# ShiftSlice.net
KiCad netlist of a schematic drawn in EAGLE
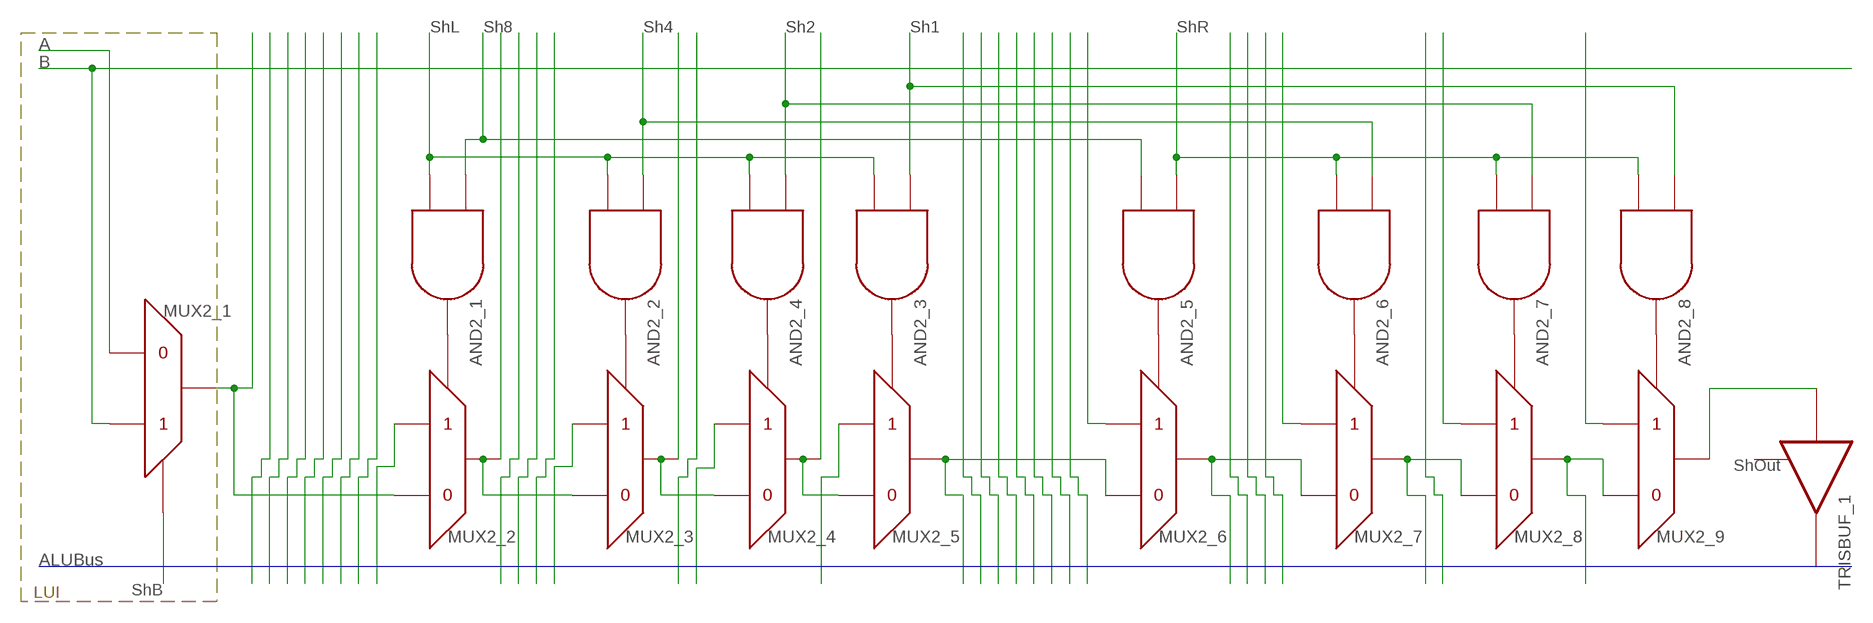
[diagram p0: schematic, sheet 1]

(export (version "E")
  (design (tool "Eeschema 10.0.6"))
  (components
    (comp (ref "AND2_1")
      (value "AND2")
      (footprint "eagle-import:3PIN")
      (libsource (lib "eagle-import") (part "AND2"))
    )
    (comp (ref "AND2_2")
      (value "AND2")
      (footprint "eagle-import:3PIN")
      (libsource (lib "eagle-import") (part "AND2"))
    )
    (comp (ref "AND2_3")
      (value "AND2")
      (footprint "eagle-import:3PIN")
      (libsource (lib "eagle-import") (part "AND2"))
    )
    (comp (ref "AND2_4")
      (value "AND2")
      (footprint "eagle-import:3PIN")
      (libsource (lib "eagle-import") (part "AND2"))
    )
    (comp (ref "AND2_5")
      (value "AND2")
      (footprint "eagle-import:3PIN")
      (libsource (lib "eagle-import") (part "AND2"))
    )
    (comp (ref "AND2_6")
      (value "AND2")
      (footprint "eagle-import:3PIN")
      (libsource (lib "eagle-import") (part "AND2"))
    )
    (comp (ref "AND2_7")
      (value "AND2")
      (footprint "eagle-import:3PIN")
      (libsource (lib "eagle-import") (part "AND2"))
    )
    (comp (ref "AND2_8")
      (value "AND2")
      (footprint "eagle-import:3PIN")
      (libsource (lib "eagle-import") (part "AND2"))
    )
    (comp (ref "MUX2_1")
      (value "MUX2")
      (footprint "eagle-import:5PIN")
      (libsource (lib "eagle-import") (part "MUX2"))
    )
    (comp (ref "MUX2_2")
      (value "MUX2")
      (footprint "eagle-import:5PIN")
      (libsource (lib "eagle-import") (part "MUX2"))
    )
    (comp (ref "MUX2_3")
      (value "MUX2")
      (footprint "eagle-import:5PIN")
      (libsource (lib "eagle-import") (part "MUX2"))
    )
    (comp (ref "MUX2_4")
      (value "MUX2")
      (footprint "eagle-import:5PIN")
      (libsource (lib "eagle-import") (part "MUX2"))
    )
    (comp (ref "MUX2_5")
      (value "MUX2")
      (footprint "eagle-import:5PIN")
      (libsource (lib "eagle-import") (part "MUX2"))
    )
    (comp (ref "MUX2_6")
      (value "MUX2")
      (footprint "eagle-import:5PIN")
      (libsource (lib "eagle-import") (part "MUX2"))
    )
    (comp (ref "MUX2_7")
      (value "MUX2")
      (footprint "eagle-import:5PIN")
      (libsource (lib "eagle-import") (part "MUX2"))
    )
    (comp (ref "MUX2_8")
      (value "MUX2")
      (footprint "eagle-import:5PIN")
      (libsource (lib "eagle-import") (part "MUX2"))
    )
    (comp (ref "MUX2_9")
      (value "MUX2")
      (footprint "eagle-import:5PIN")
      (libsource (lib "eagle-import") (part "MUX2"))
    )
    (comp (ref "TRISBUF_1")
      (value "TRISBUF")
      (footprint "eagle-import:3PIN")
      (libsource (lib "eagle-import") (part "TRISBUF"))
    )
  )
  (nets
    (net (code "1") (name "Net-(AND2_1-A)") (class "Default")
      (node (ref "AND2_1") (pin "P$1") (pinfunction "A_P$1") (pintype "input"))
      (node (ref "AND2_5") (pin "P$2") (pinfunction "I1_P$2") (pintype "input"))
    )
    (net (code "2") (name "Net-(AND2_1-I1)") (class "Default")
      (node (ref "AND2_1") (pin "P$2") (pinfunction "I1_P$2") (pintype "input"))
      (node (ref "AND2_2") (pin "P$2") (pinfunction "I1_P$2") (pintype "input"))
      (node (ref "AND2_3") (pin "P$2") (pinfunction "I1_P$2") (pintype "input"))
      (node (ref "AND2_4") (pin "P$2") (pinfunction "I1_P$2") (pintype "input"))
    )
    (net (code "3") (name "Net-(AND2_1-O)") (class "Default")
      (node (ref "AND2_1") (pin "P$3") (pinfunction "O_P$3") (pintype "output"))
      (node (ref "MUX2_2") (pin "P$4") (pinfunction "P$4_P$4") (pintype "bidirectional"))
    )
    (net (code "4") (name "Net-(AND2_2-A)") (class "Default")
      (node (ref "AND2_2") (pin "P$1") (pinfunction "A_P$1") (pintype "input"))
      (node (ref "AND2_6") (pin "P$1") (pinfunction "A_P$1") (pintype "input"))
    )
    (net (code "5") (name "Net-(AND2_2-O)") (class "Default")
      (node (ref "AND2_2") (pin "P$3") (pinfunction "O_P$3") (pintype "output"))
      (node (ref "MUX2_3") (pin "P$4") (pinfunction "P$4_P$4") (pintype "bidirectional"))
    )
    (net (code "6") (name "Net-(AND2_3-A)") (class "Default")
      (node (ref "AND2_3") (pin "P$1") (pinfunction "A_P$1") (pintype "input"))
      (node (ref "AND2_8") (pin "P$1") (pinfunction "A_P$1") (pintype "input"))
    )
    (net (code "7") (name "Net-(AND2_3-O)") (class "Default")
      (node (ref "AND2_3") (pin "P$3") (pinfunction "O_P$3") (pintype "output"))
      (node (ref "MUX2_5") (pin "P$4") (pinfunction "P$4_P$4") (pintype "bidirectional"))
    )
    (net (code "8") (name "Net-(AND2_4-A)") (class "Default")
      (node (ref "AND2_4") (pin "P$1") (pinfunction "A_P$1") (pintype "input"))
      (node (ref "AND2_7") (pin "P$1") (pinfunction "A_P$1") (pintype "input"))
    )
    (net (code "9") (name "Net-(AND2_4-O)") (class "Default")
      (node (ref "AND2_4") (pin "P$3") (pinfunction "O_P$3") (pintype "output"))
      (node (ref "MUX2_4") (pin "P$4") (pinfunction "P$4_P$4") (pintype "bidirectional"))
    )
    (net (code "10") (name "Net-(AND2_5-A)") (class "Default")
      (node (ref "AND2_5") (pin "P$1") (pinfunction "A_P$1") (pintype "input"))
      (node (ref "AND2_6") (pin "P$2") (pinfunction "I1_P$2") (pintype "input"))
      (node (ref "AND2_7") (pin "P$2") (pinfunction "I1_P$2") (pintype "input"))
      (node (ref "AND2_8") (pin "P$2") (pinfunction "I1_P$2") (pintype "input"))
    )
    (net (code "11") (name "Net-(AND2_5-O)") (class "Default")
      (node (ref "AND2_5") (pin "P$3") (pinfunction "O_P$3") (pintype "output"))
      (node (ref "MUX2_6") (pin "P$4") (pinfunction "P$4_P$4") (pintype "bidirectional"))
    )
    (net (code "12") (name "Net-(AND2_6-O)") (class "Default")
      (node (ref "AND2_6") (pin "P$3") (pinfunction "O_P$3") (pintype "output"))
      (node (ref "MUX2_7") (pin "P$4") (pinfunction "P$4_P$4") (pintype "bidirectional"))
    )
    (net (code "13") (name "Net-(AND2_7-O)") (class "Default")
      (node (ref "AND2_7") (pin "P$3") (pinfunction "O_P$3") (pintype "output"))
      (node (ref "MUX2_8") (pin "P$4") (pinfunction "P$4_P$4") (pintype "bidirectional"))
    )
    (net (code "14") (name "Net-(AND2_8-O)") (class "Default")
      (node (ref "AND2_8") (pin "P$3") (pinfunction "O_P$3") (pintype "output"))
      (node (ref "MUX2_9") (pin "P$4") (pinfunction "P$4_P$4") (pintype "bidirectional"))
    )
    (net (code "15") (name "Net-(MUX2_1-PadP$3)") (class "Default")
      (node (ref "MUX2_1") (pin "P$3") (pinfunction "P$3_P$3") (pintype "bidirectional"))
      (node (ref "MUX2_2") (pin "P$1") (pinfunction "P$1_P$1") (pintype "bidirectional"))
    )
    (net (code "16") (name "Net-(MUX2_5-PadP$3)") (class "Default")
      (node (ref "MUX2_5") (pin "P$3") (pinfunction "P$3_P$3") (pintype "bidirectional"))
      (node (ref "MUX2_6") (pin "P$1") (pinfunction "P$1_P$1") (pintype "bidirectional"))
    )
    (net (code "17") (name "Net-(MUX2_6-PadP$3)") (class "Default")
      (node (ref "MUX2_6") (pin "P$3") (pinfunction "P$3_P$3") (pintype "bidirectional"))
      (node (ref "MUX2_7") (pin "P$1") (pinfunction "P$1_P$1") (pintype "bidirectional"))
    )
    (net (code "18") (name "Net-(MUX2_7-PadP$3)") (class "Default")
      (node (ref "MUX2_7") (pin "P$3") (pinfunction "P$3_P$3") (pintype "bidirectional"))
      (node (ref "MUX2_8") (pin "P$1") (pinfunction "P$1_P$1") (pintype "bidirectional"))
    )
    (net (code "19") (name "Net-(MUX2_8-PadP$3)") (class "Default")
      (node (ref "MUX2_8") (pin "P$3") (pinfunction "P$3_P$3") (pintype "bidirectional"))
      (node (ref "MUX2_9") (pin "P$1") (pinfunction "P$1_P$1") (pintype "bidirectional"))
    )
    (net (code "20") (name "Net-(TRISBUF_1-I)") (class "Default")
      (node (ref "MUX2_9") (pin "P$3") (pinfunction "P$3_P$3") (pintype "bidirectional"))
      (node (ref "TRISBUF_1") (pin "P$1") (pinfunction "I_P$1") (pintype "input"))
    )
    (net (code "21") (name "unconnected-(MUX2_1-PadP$1)") (class "Default")
      (node (ref "MUX2_1") (pin "P$1") (pinfunction "P$1_P$1") (pintype "bidirectional"))
    )
    (net (code "22") (name "unconnected-(MUX2_1-PadP$2)") (class "Default")
      (node (ref "MUX2_1") (pin "P$2") (pinfunction "P$2_P$2") (pintype "bidirectional"))
    )
    (net (code "23") (name "unconnected-(MUX2_1-PadP$4)") (class "Default")
      (node (ref "MUX2_1") (pin "P$4") (pinfunction "P$4_P$4") (pintype "bidirectional"))
    )
    (net (code "24") (name "unconnected-(MUX2_2-PadP$2)") (class "Default")
      (node (ref "MUX2_2") (pin "P$2") (pinfunction "P$2_P$2") (pintype "bidirectional"))
    )
    (net (code "25") (name "unconnected-(MUX2_2-PadP$3)") (class "Default")
      (node (ref "MUX2_2") (pin "P$3") (pinfunction "P$3_P$3") (pintype "bidirectional"))
    )
    (net (code "26") (name "unconnected-(MUX2_3-PadP$1)") (class "Default")
      (node (ref "MUX2_3") (pin "P$1") (pinfunction "P$1_P$1") (pintype "bidirectional"))
    )
    (net (code "27") (name "unconnected-(MUX2_3-PadP$2)") (class "Default")
      (node (ref "MUX2_3") (pin "P$2") (pinfunction "P$2_P$2") (pintype "bidirectional"))
    )
    (net (code "28") (name "unconnected-(MUX2_3-PadP$3)") (class "Default")
      (node (ref "MUX2_3") (pin "P$3") (pinfunction "P$3_P$3") (pintype "bidirectional"))
    )
    (net (code "29") (name "unconnected-(MUX2_4-PadP$1)") (class "Default")
      (node (ref "MUX2_4") (pin "P$1") (pinfunction "P$1_P$1") (pintype "bidirectional"))
    )
    (net (code "30") (name "unconnected-(MUX2_4-PadP$2)") (class "Default")
      (node (ref "MUX2_4") (pin "P$2") (pinfunction "P$2_P$2") (pintype "bidirectional"))
    )
    (net (code "31") (name "unconnected-(MUX2_4-PadP$3)") (class "Default")
      (node (ref "MUX2_4") (pin "P$3") (pinfunction "P$3_P$3") (pintype "bidirectional"))
    )
    (net (code "32") (name "unconnected-(MUX2_5-PadP$1)") (class "Default")
      (node (ref "MUX2_5") (pin "P$1") (pinfunction "P$1_P$1") (pintype "bidirectional"))
    )
    (net (code "33") (name "unconnected-(MUX2_5-PadP$2)") (class "Default")
      (node (ref "MUX2_5") (pin "P$2") (pinfunction "P$2_P$2") (pintype "bidirectional"))
    )
    (net (code "34") (name "unconnected-(MUX2_6-PadP$2)") (class "Default")
      (node (ref "MUX2_6") (pin "P$2") (pinfunction "P$2_P$2") (pintype "bidirectional"))
    )
    (net (code "35") (name "unconnected-(MUX2_7-PadP$2)") (class "Default")
      (node (ref "MUX2_7") (pin "P$2") (pinfunction "P$2_P$2") (pintype "bidirectional"))
    )
    (net (code "36") (name "unconnected-(MUX2_8-PadP$2)") (class "Default")
      (node (ref "MUX2_8") (pin "P$2") (pinfunction "P$2_P$2") (pintype "bidirectional"))
    )
    (net (code "37") (name "unconnected-(MUX2_9-PadP$2)") (class "Default")
      (node (ref "MUX2_9") (pin "P$2") (pinfunction "P$2_P$2") (pintype "bidirectional"))
    )
    (net (code "38") (name "unconnected-(TRISBUF_1-O-PadP$2)") (class "Default")
      (node (ref "TRISBUF_1") (pin "P$2") (pinfunction "O_P$2") (pintype "open_collector"))
    )
    (net (code "39") (name "unconnected-(TRISBUF_1-P$1-PadP$3)") (class "Default")
      (node (ref "TRISBUF_1") (pin "P$3") (pinfunction "P$1_P$3") (pintype "bidirectional"))
    )
  )
)
